# RasPi-BplusHAT.net
KiCad netlist of a schematic drawn in EAGLE
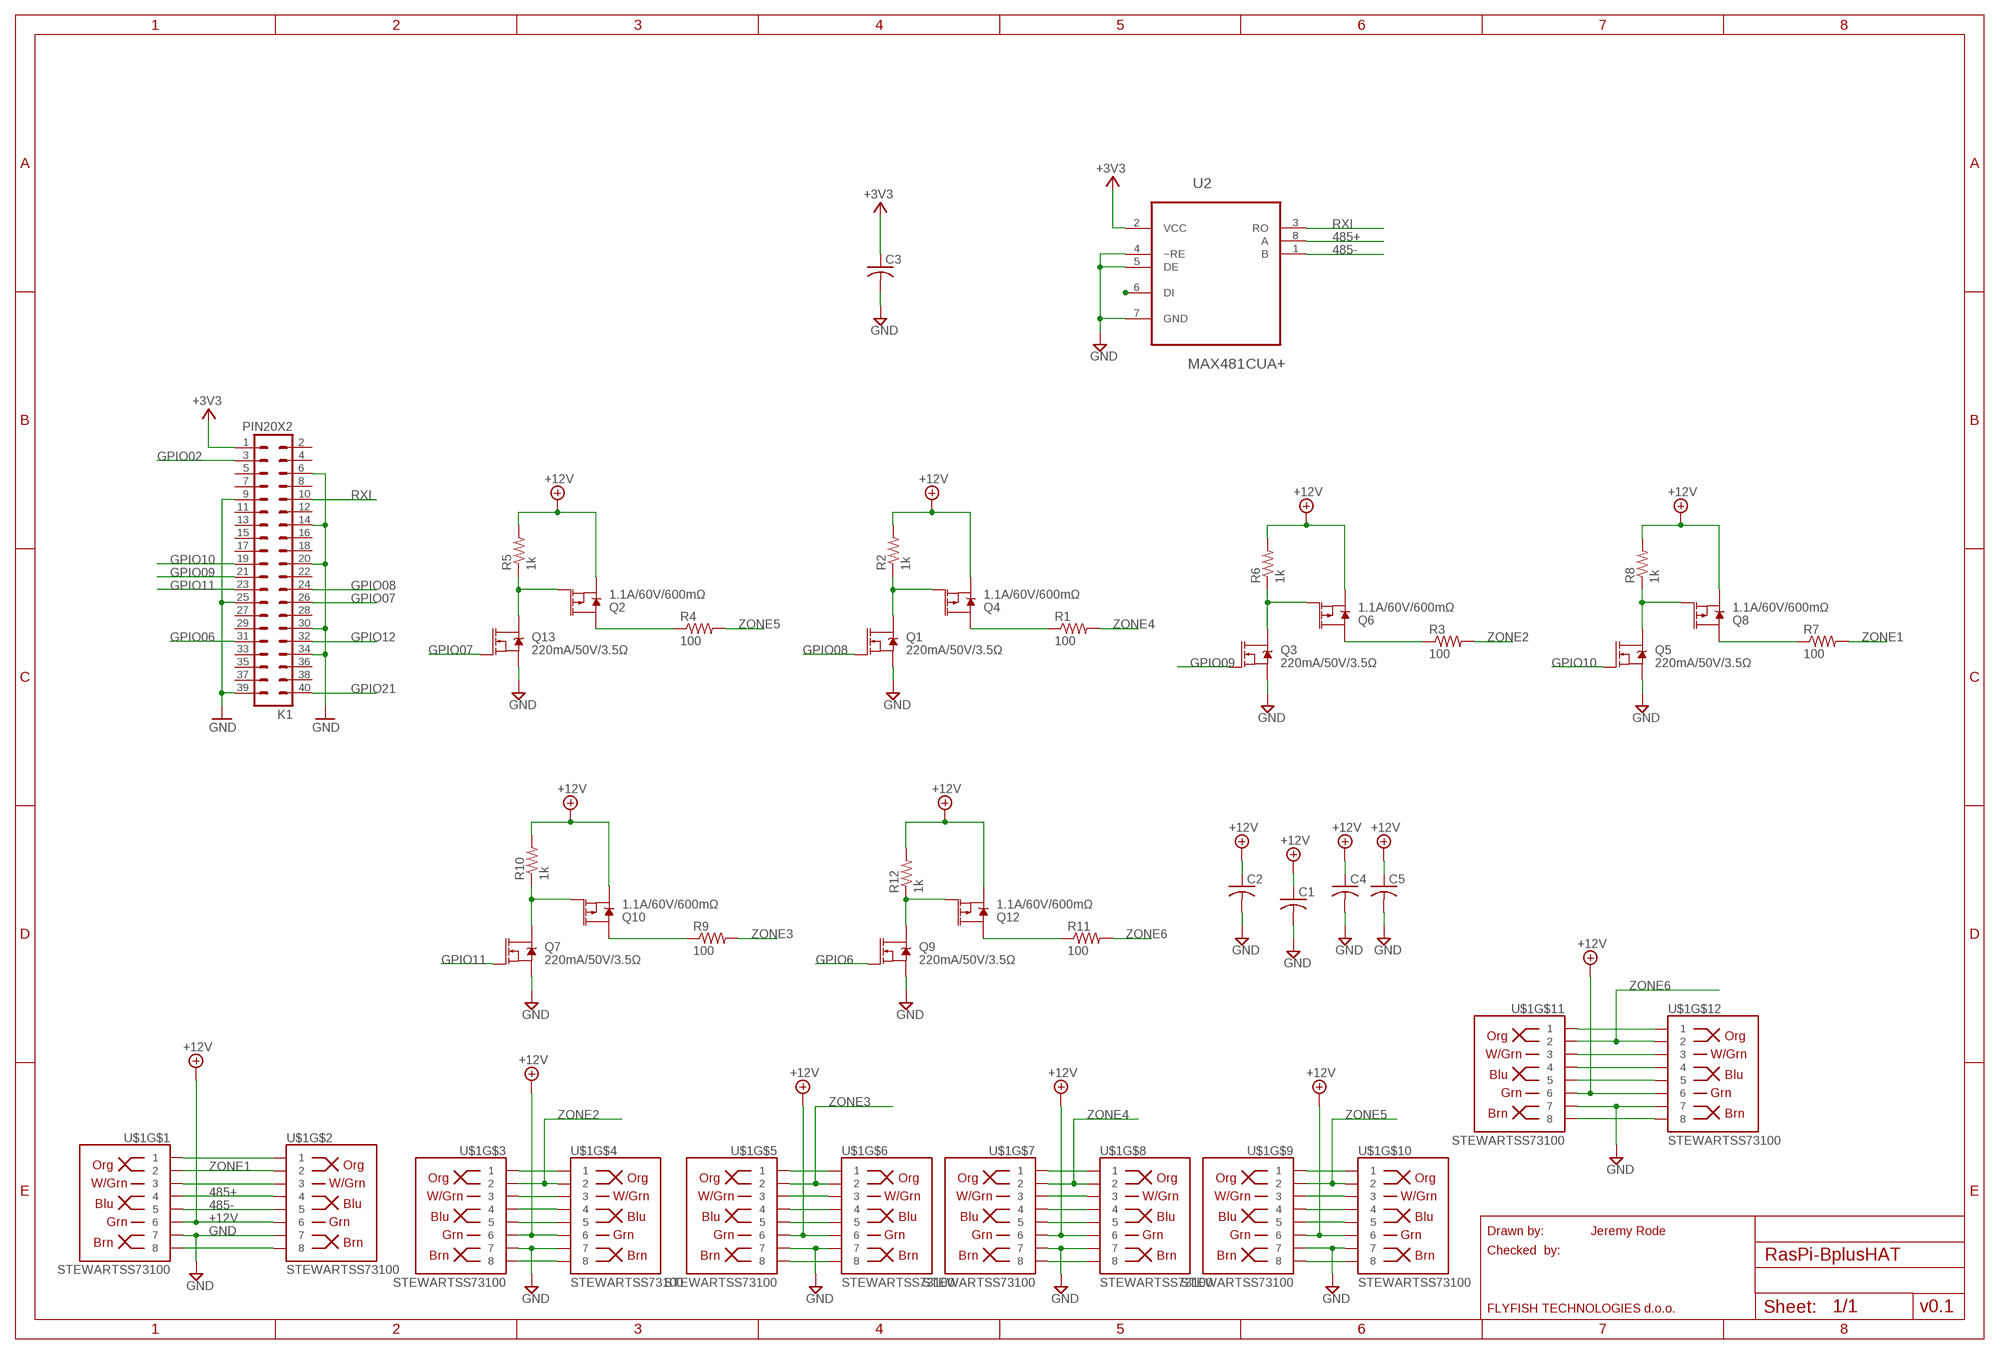
[diagram p0: schematic, sheet 1]

(export (version "E")
  (design (tool "Eeschema 10.0.6"))
  (components
    (comp (ref "C1")
      (value "C-USC0805")
      (footprint "eagle-import:C0805")
      (libsource (lib "eagle-import") (part "C-USC0805"))
    )
    (comp (ref "C2")
      (value "C-USC0805")
      (footprint "eagle-import:C0805")
      (libsource (lib "eagle-import") (part "C-USC0805"))
    )
    (comp (ref "C3")
      (value "C-USC0805")
      (footprint "eagle-import:C0805")
      (libsource (lib "eagle-import") (part "C-USC0805"))
    )
    (comp (ref "C4")
      (value "C-USC0805")
      (footprint "eagle-import:C0805")
      (libsource (lib "eagle-import") (part "C-USC0805"))
    )
    (comp (ref "C5")
      (value "C-USC0805")
      (footprint "eagle-import:C0805")
      (libsource (lib "eagle-import") (part "C-USC0805"))
    )
    (comp (ref "K1")
      (value "PIN20X2")
      (footprint "eagle-import:PIN_20X2")
      (libsource (lib "eagle-import") (part "PIN20X2"))
    )
    (comp (ref "Q1")
      (value "220mA/50V/3.5Ω")
      (footprint "eagle-import:SOT23-3")
      (libsource (lib "eagle-import") (part "MOSFET-NCH-BSS138"))
    )
    (comp (ref "Q2")
      (value "1.1A/60V/600mΩ")
      (footprint "eagle-import:SOT23-3")
      (libsource (lib "eagle-import") (part "MOSFET_PCH-SI2309DS"))
    )
    (comp (ref "Q3")
      (value "220mA/50V/3.5Ω")
      (footprint "eagle-import:SOT23-3")
      (libsource (lib "eagle-import") (part "MOSFET-NCH-BSS138"))
    )
    (comp (ref "Q4")
      (value "1.1A/60V/600mΩ")
      (footprint "eagle-import:SOT23-3")
      (libsource (lib "eagle-import") (part "MOSFET_PCH-SI2309DS"))
    )
    (comp (ref "Q5")
      (value "220mA/50V/3.5Ω")
      (footprint "eagle-import:SOT23-3")
      (libsource (lib "eagle-import") (part "MOSFET-NCH-BSS138"))
    )
    (comp (ref "Q6")
      (value "1.1A/60V/600mΩ")
      (footprint "eagle-import:SOT23-3")
      (libsource (lib "eagle-import") (part "MOSFET_PCH-SI2309DS"))
    )
    (comp (ref "Q7")
      (value "220mA/50V/3.5Ω")
      (footprint "eagle-import:SOT23-3")
      (libsource (lib "eagle-import") (part "MOSFET-NCH-BSS138"))
    )
    (comp (ref "Q8")
      (value "1.1A/60V/600mΩ")
      (footprint "eagle-import:SOT23-3")
      (libsource (lib "eagle-import") (part "MOSFET_PCH-SI2309DS"))
    )
    (comp (ref "Q9")
      (value "220mA/50V/3.5Ω")
      (footprint "eagle-import:SOT23-3")
      (libsource (lib "eagle-import") (part "MOSFET-NCH-BSS138"))
    )
    (comp (ref "Q10")
      (value "1.1A/60V/600mΩ")
      (footprint "eagle-import:SOT23-3")
      (libsource (lib "eagle-import") (part "MOSFET_PCH-SI2309DS"))
    )
    (comp (ref "Q12")
      (value "1.1A/60V/600mΩ")
      (footprint "eagle-import:SOT23-3")
      (libsource (lib "eagle-import") (part "MOSFET_PCH-SI2309DS"))
    )
    (comp (ref "Q13")
      (value "220mA/50V/3.5Ω")
      (footprint "eagle-import:SOT23-3")
      (libsource (lib "eagle-import") (part "MOSFET-NCH-BSS138"))
    )
    (comp (ref "R1")
      (value "100")
      (footprint "eagle-import:R0805")
      (libsource (lib "eagle-import") (part "R-US_R0805"))
    )
    (comp (ref "R2")
      (value "1k")
      (footprint "eagle-import:R0805")
      (libsource (lib "eagle-import") (part "R-US_R0805"))
    )
    (comp (ref "R3")
      (value "100")
      (footprint "eagle-import:R0805")
      (libsource (lib "eagle-import") (part "R-US_R0805"))
    )
    (comp (ref "R4")
      (value "100")
      (footprint "eagle-import:R0805")
      (libsource (lib "eagle-import") (part "R-US_R0805"))
    )
    (comp (ref "R5")
      (value "1k")
      (footprint "eagle-import:R0805")
      (libsource (lib "eagle-import") (part "R-US_R0805"))
    )
    (comp (ref "R6")
      (value "1k")
      (footprint "eagle-import:R0805")
      (libsource (lib "eagle-import") (part "R-US_R0805"))
    )
    (comp (ref "R7")
      (value "100")
      (footprint "eagle-import:R0805")
      (libsource (lib "eagle-import") (part "R-US_R0805"))
    )
    (comp (ref "R8")
      (value "1k")
      (footprint "eagle-import:R0805")
      (libsource (lib "eagle-import") (part "R-US_R0805"))
    )
    (comp (ref "R9")
      (value "100")
      (footprint "eagle-import:R0805")
      (libsource (lib "eagle-import") (part "R-US_R0805"))
    )
    (comp (ref "R10")
      (value "1k")
      (footprint "eagle-import:R0805")
      (libsource (lib "eagle-import") (part "R-US_R0805"))
    )
    (comp (ref "R11")
      (value "100")
      (footprint "eagle-import:R0805")
      (libsource (lib "eagle-import") (part "R-US_R0805"))
    )
    (comp (ref "R12")
      (value "1k")
      (footprint "eagle-import:R0805")
      (libsource (lib "eagle-import") (part "R-US_R0805"))
    )
    (comp (ref "U$1")
      (value "STEWARTSS73100")
      (footprint "eagle-import:STEWARTSS73100")
      (libsource (lib "eagle-import") (part "STEWARTSS73100"))
    )
    (comp (ref "U2")
      (value "MAX481CUA+")
      (footprint "eagle-import:SOP65P490X110-8N")
      (fields (field (name "MF") "Maxim Integrated"))
      (libsource (lib "eagle-import") (part "MAX481CUA+"))
    )
  )
  (nets
    (net (code "1") (name "+3V3") (class "Default")
      (node (ref "C3") (pin "1") (pinfunction "1_1") (pintype "passive"))
      (node (ref "K1") (pin "1") (pinfunction "1_1") (pintype "passive"))
      (node (ref "U2") (pin "2") (pinfunction "VCC_2") (pintype "power_in"))
    )
    (net (code "2") (name "+12V") (class "Default")
      (node (ref "C1") (pin "1") (pinfunction "1_1") (pintype "passive"))
      (node (ref "C2") (pin "1") (pinfunction "1_1") (pintype "passive"))
      (node (ref "C4") (pin "1") (pinfunction "1_1") (pintype "passive"))
      (node (ref "C5") (pin "1") (pinfunction "1_1") (pintype "passive"))
      (node (ref "Q10") (pin "2") (pinfunction "S_2") (pintype "bidirectional"))
      (node (ref "Q12") (pin "2") (pinfunction "S_2") (pintype "bidirectional"))
      (node (ref "Q2") (pin "2") (pinfunction "S_2") (pintype "bidirectional"))
      (node (ref "Q4") (pin "2") (pinfunction "S_2") (pintype "bidirectional"))
      (node (ref "Q6") (pin "2") (pinfunction "S_2") (pintype "bidirectional"))
      (node (ref "Q8") (pin "2") (pinfunction "S_2") (pintype "bidirectional"))
      (node (ref "R10") (pin "2") (pinfunction "2_2") (pintype "passive"))
      (node (ref "R12") (pin "2") (pinfunction "2_2") (pintype "passive"))
      (node (ref "R2") (pin "2") (pinfunction "2_2") (pintype "passive"))
      (node (ref "R5") (pin "2") (pinfunction "2_2") (pintype "passive"))
      (node (ref "R6") (pin "2") (pinfunction "2_2") (pintype "passive"))
      (node (ref "R8") (pin "2") (pinfunction "2_2") (pintype "passive"))
      (node (ref "U$1") (pin "P$14") (pinfunction "6_P$14") (pintype "bidirectional"))
      (node (ref "U$1") (pin "P$22") (pinfunction "6_P$22") (pintype "bidirectional"))
      (node (ref "U$1") (pin "P$30") (pinfunction "6_P$30") (pintype "bidirectional"))
      (node (ref "U$1") (pin "P$38") (pinfunction "6_P$38") (pintype "bidirectional"))
      (node (ref "U$1") (pin "P$46") (pinfunction "6_P$46") (pintype "bidirectional"))
      (node (ref "U$1") (pin "P$54") (pinfunction "6_P$54") (pintype "bidirectional"))
      (node (ref "U$1") (pin "P$6") (pinfunction "6_P$6") (pintype "bidirectional"))
      (node (ref "U$1") (pin "P$62") (pinfunction "6_P$62") (pintype "bidirectional"))
      (node (ref "U$1") (pin "P$70") (pinfunction "6_P$70") (pintype "bidirectional"))
      (node (ref "U$1") (pin "P$78") (pinfunction "6_P$78") (pintype "bidirectional"))
      (node (ref "U$1") (pin "P$86") (pinfunction "6_P$86") (pintype "bidirectional"))
      (node (ref "U$1") (pin "P$94") (pinfunction "6_P$94") (pintype "bidirectional"))
    )
    (net (code "3") (name "/485+") (class "Default")
      (node (ref "U$1") (pin "P$12") (pinfunction "4_P$12") (pintype "bidirectional"))
      (node (ref "U$1") (pin "P$4") (pinfunction "4_P$4") (pintype "bidirectional"))
      (node (ref "U2") (pin "8") (pinfunction "A_8") (pintype "bidirectional"))
    )
    (net (code "4") (name "/485-") (class "Default")
      (node (ref "U$1") (pin "P$13") (pinfunction "5_P$13") (pintype "bidirectional"))
      (node (ref "U$1") (pin "P$5") (pinfunction "5_P$5") (pintype "bidirectional"))
      (node (ref "U2") (pin "1") (pinfunction "B_1") (pintype "bidirectional"))
    )
    (net (code "5") (name "/GPIO02") (class "Default")
      (node (ref "K1") (pin "3") (pinfunction "3_3") (pintype "passive"))
    )
    (net (code "6") (name "/GPIO06") (class "Default")
      (node (ref "K1") (pin "31") (pinfunction "31_31") (pintype "passive"))
    )
    (net (code "7") (name "/GPIO6") (class "Default")
      (node (ref "Q9") (pin "1") (pinfunction "G_1") (pintype "bidirectional"))
    )
    (net (code "8") (name "/GPIO07") (class "Default")
      (node (ref "K1") (pin "26") (pinfunction "26_26") (pintype "passive"))
      (node (ref "Q13") (pin "1") (pinfunction "G_1") (pintype "bidirectional"))
    )
    (net (code "9") (name "/GPIO08") (class "Default")
      (node (ref "K1") (pin "24") (pinfunction "24_24") (pintype "passive"))
      (node (ref "Q1") (pin "1") (pinfunction "G_1") (pintype "bidirectional"))
    )
    (net (code "10") (name "/GPIO09") (class "Default")
      (node (ref "K1") (pin "21") (pinfunction "21_21") (pintype "passive"))
      (node (ref "Q3") (pin "1") (pinfunction "G_1") (pintype "bidirectional"))
    )
    (net (code "11") (name "/GPIO10") (class "Default")
      (node (ref "K1") (pin "19") (pinfunction "19_19") (pintype "passive"))
      (node (ref "Q5") (pin "1") (pinfunction "G_1") (pintype "bidirectional"))
    )
    (net (code "12") (name "/GPIO11") (class "Default")
      (node (ref "K1") (pin "23") (pinfunction "23_23") (pintype "passive"))
      (node (ref "Q7") (pin "1") (pinfunction "G_1") (pintype "bidirectional"))
    )
    (net (code "13") (name "/GPIO12") (class "Default")
      (node (ref "K1") (pin "32") (pinfunction "32_32") (pintype "passive"))
    )
    (net (code "14") (name "/GPIO21") (class "Default")
      (node (ref "K1") (pin "40") (pinfunction "40_40") (pintype "passive"))
    )
    (net (code "15") (name "/RXI") (class "Default")
      (node (ref "K1") (pin "10") (pinfunction "10_10") (pintype "passive"))
      (node (ref "U2") (pin "3") (pinfunction "RO_3") (pintype "output"))
    )
    (net (code "16") (name "/ZONE1") (class "Default")
      (node (ref "R7") (pin "2") (pinfunction "2_2") (pintype "passive"))
      (node (ref "U$1") (pin "P$10") (pinfunction "2_P$10") (pintype "bidirectional"))
      (node (ref "U$1") (pin "P$2") (pinfunction "2_P$2") (pintype "bidirectional"))
    )
    (net (code "17") (name "/ZONE2") (class "Default")
      (node (ref "R3") (pin "2") (pinfunction "2_2") (pintype "passive"))
      (node (ref "U$1") (pin "P$18") (pinfunction "2_P$18") (pintype "bidirectional"))
      (node (ref "U$1") (pin "P$26") (pinfunction "2_P$26") (pintype "bidirectional"))
    )
    (net (code "18") (name "/ZONE3") (class "Default")
      (node (ref "R9") (pin "2") (pinfunction "2_2") (pintype "passive"))
      (node (ref "U$1") (pin "P$34") (pinfunction "2_P$34") (pintype "bidirectional"))
      (node (ref "U$1") (pin "P$42") (pinfunction "2_P$42") (pintype "bidirectional"))
    )
    (net (code "19") (name "/ZONE4") (class "Default")
      (node (ref "R1") (pin "2") (pinfunction "2_2") (pintype "passive"))
      (node (ref "U$1") (pin "P$50") (pinfunction "2_P$50") (pintype "bidirectional"))
      (node (ref "U$1") (pin "P$58") (pinfunction "2_P$58") (pintype "bidirectional"))
    )
    (net (code "20") (name "/ZONE5") (class "Default")
      (node (ref "R4") (pin "2") (pinfunction "2_2") (pintype "passive"))
      (node (ref "U$1") (pin "P$66") (pinfunction "2_P$66") (pintype "bidirectional"))
      (node (ref "U$1") (pin "P$74") (pinfunction "2_P$74") (pintype "bidirectional"))
    )
    (net (code "21") (name "/ZONE6") (class "Default")
      (node (ref "R11") (pin "2") (pinfunction "2_2") (pintype "passive"))
      (node (ref "U$1") (pin "P$82") (pinfunction "2_P$82") (pintype "bidirectional"))
      (node (ref "U$1") (pin "P$90") (pinfunction "2_P$90") (pintype "bidirectional"))
    )
    (net (code "22") (name "GND") (class "Default")
      (node (ref "C1") (pin "2") (pinfunction "2_2") (pintype "passive"))
      (node (ref "C2") (pin "2") (pinfunction "2_2") (pintype "passive"))
      (node (ref "C3") (pin "2") (pinfunction "2_2") (pintype "passive"))
      (node (ref "C4") (pin "2") (pinfunction "2_2") (pintype "passive"))
      (node (ref "C5") (pin "2") (pinfunction "2_2") (pintype "passive"))
      (node (ref "K1") (pin "14") (pinfunction "14_14") (pintype "passive"))
      (node (ref "K1") (pin "20") (pinfunction "20_20") (pintype "passive"))
      (node (ref "K1") (pin "25") (pinfunction "25_25") (pintype "passive"))
      (node (ref "K1") (pin "30") (pinfunction "30_30") (pintype "passive"))
      (node (ref "K1") (pin "34") (pinfunction "34_34") (pintype "passive"))
      (node (ref "K1") (pin "39") (pinfunction "39_39") (pintype "passive"))
      (node (ref "K1") (pin "6") (pinfunction "6_6") (pintype "passive"))
      (node (ref "K1") (pin "9") (pinfunction "9_9") (pintype "passive"))
      (node (ref "Q1") (pin "2") (pinfunction "S_2") (pintype "bidirectional"))
      (node (ref "Q13") (pin "2") (pinfunction "S_2") (pintype "bidirectional"))
      (node (ref "Q3") (pin "2") (pinfunction "S_2") (pintype "bidirectional"))
      (node (ref "Q5") (pin "2") (pinfunction "S_2") (pintype "bidirectional"))
      (node (ref "Q7") (pin "2") (pinfunction "S_2") (pintype "bidirectional"))
      (node (ref "Q9") (pin "2") (pinfunction "S_2") (pintype "bidirectional"))
      (node (ref "U$1") (pin "P$15") (pinfunction "7_P$15") (pintype "bidirectional"))
      (node (ref "U$1") (pin "P$23") (pinfunction "7_P$23") (pintype "bidirectional"))
      (node (ref "U$1") (pin "P$31") (pinfunction "7_P$31") (pintype "bidirectional"))
      (node (ref "U$1") (pin "P$39") (pinfunction "7_P$39") (pintype "bidirectional"))
      (node (ref "U$1") (pin "P$47") (pinfunction "7_P$47") (pintype "bidirectional"))
      (node (ref "U$1") (pin "P$55") (pinfunction "7_P$55") (pintype "bidirectional"))
      (node (ref "U$1") (pin "P$63") (pinfunction "7_P$63") (pintype "bidirectional"))
      (node (ref "U$1") (pin "P$7") (pinfunction "7_P$7") (pintype "bidirectional"))
      (node (ref "U$1") (pin "P$71") (pinfunction "7_P$71") (pintype "bidirectional"))
      (node (ref "U$1") (pin "P$79") (pinfunction "7_P$79") (pintype "bidirectional"))
      (node (ref "U$1") (pin "P$87") (pinfunction "7_P$87") (pintype "bidirectional"))
      (node (ref "U$1") (pin "P$95") (pinfunction "7_P$95") (pintype "bidirectional"))
      (node (ref "U2") (pin "4") (pinfunction "~{RE}_4") (pintype "input"))
      (node (ref "U2") (pin "5") (pinfunction "DE_5") (pintype "input"))
      (node (ref "U2") (pin "7") (pinfunction "GND_7") (pintype "passive"))
    )
    (net (code "23") (name "Net-(Q1-D)") (class "Default")
      (node (ref "Q1") (pin "3") (pinfunction "D_3") (pintype "bidirectional"))
      (node (ref "Q4") (pin "1") (pinfunction "G_1") (pintype "bidirectional"))
      (node (ref "R2") (pin "1") (pinfunction "1_1") (pintype "passive"))
    )
    (net (code "24") (name "Net-(Q2-D)") (class "Default")
      (node (ref "Q2") (pin "3") (pinfunction "D_3") (pintype "bidirectional"))
      (node (ref "R4") (pin "1") (pinfunction "1_1") (pintype "passive"))
    )
    (net (code "25") (name "Net-(Q3-D)") (class "Default")
      (node (ref "Q3") (pin "3") (pinfunction "D_3") (pintype "bidirectional"))
      (node (ref "Q6") (pin "1") (pinfunction "G_1") (pintype "bidirectional"))
      (node (ref "R6") (pin "1") (pinfunction "1_1") (pintype "passive"))
    )
    (net (code "26") (name "Net-(Q4-D)") (class "Default")
      (node (ref "Q4") (pin "3") (pinfunction "D_3") (pintype "bidirectional"))
      (node (ref "R1") (pin "1") (pinfunction "1_1") (pintype "passive"))
    )
    (net (code "27") (name "Net-(Q5-D)") (class "Default")
      (node (ref "Q5") (pin "3") (pinfunction "D_3") (pintype "bidirectional"))
      (node (ref "Q8") (pin "1") (pinfunction "G_1") (pintype "bidirectional"))
      (node (ref "R8") (pin "1") (pinfunction "1_1") (pintype "passive"))
    )
    (net (code "28") (name "Net-(Q6-D)") (class "Default")
      (node (ref "Q6") (pin "3") (pinfunction "D_3") (pintype "bidirectional"))
      (node (ref "R3") (pin "1") (pinfunction "1_1") (pintype "passive"))
    )
    (net (code "29") (name "Net-(Q8-D)") (class "Default")
      (node (ref "Q8") (pin "3") (pinfunction "D_3") (pintype "bidirectional"))
      (node (ref "R7") (pin "1") (pinfunction "1_1") (pintype "passive"))
    )
    (net (code "30") (name "Net-(Q10-D)") (class "Default")
      (node (ref "Q10") (pin "3") (pinfunction "D_3") (pintype "bidirectional"))
      (node (ref "R9") (pin "1") (pinfunction "1_1") (pintype "passive"))
    )
    (net (code "31") (name "Net-(Q10-G)") (class "Default")
      (node (ref "Q10") (pin "1") (pinfunction "G_1") (pintype "bidirectional"))
      (node (ref "Q7") (pin "3") (pinfunction "D_3") (pintype "bidirectional"))
      (node (ref "R10") (pin "1") (pinfunction "1_1") (pintype "passive"))
    )
    (net (code "32") (name "Net-(Q12-D)") (class "Default")
      (node (ref "Q12") (pin "3") (pinfunction "D_3") (pintype "bidirectional"))
      (node (ref "R11") (pin "1") (pinfunction "1_1") (pintype "passive"))
    )
    (net (code "33") (name "Net-(Q12-G)") (class "Default")
      (node (ref "Q12") (pin "1") (pinfunction "G_1") (pintype "bidirectional"))
      (node (ref "Q9") (pin "3") (pinfunction "D_3") (pintype "bidirectional"))
      (node (ref "R12") (pin "1") (pinfunction "1_1") (pintype "passive"))
    )
    (net (code "34") (name "Net-(Q13-D)") (class "Default")
      (node (ref "Q13") (pin "3") (pinfunction "D_3") (pintype "bidirectional"))
      (node (ref "Q2") (pin "1") (pinfunction "G_1") (pintype "bidirectional"))
      (node (ref "R5") (pin "1") (pinfunction "1_1") (pintype "passive"))
    )
    (net (code "35") (name "Net-(U$1A-1)") (class "Default")
      (node (ref "U$1") (pin "P$1") (pinfunction "1_P$1") (pintype "bidirectional"))
      (node (ref "U$1") (pin "P$9") (pinfunction "1_P$9") (pintype "bidirectional"))
    )
    (net (code "36") (name "Net-(U$1A-3)") (class "Default")
      (node (ref "U$1") (pin "P$11") (pinfunction "3_P$11") (pintype "bidirectional"))
      (node (ref "U$1") (pin "P$3") (pinfunction "3_P$3") (pintype "bidirectional"))
    )
    (net (code "37") (name "Net-(U$1A-8)") (class "Default")
      (node (ref "U$1") (pin "P$16") (pinfunction "8_P$16") (pintype "bidirectional"))
      (node (ref "U$1") (pin "P$8") (pinfunction "8_P$8") (pintype "bidirectional"))
    )
    (net (code "38") (name "Net-(U$1B-1)") (class "Default")
      (node (ref "U$1") (pin "P$65") (pinfunction "1_P$65") (pintype "bidirectional"))
      (node (ref "U$1") (pin "P$73") (pinfunction "1_P$73") (pintype "bidirectional"))
    )
    (net (code "39") (name "Net-(U$1B-3)") (class "Default")
      (node (ref "U$1") (pin "P$67") (pinfunction "3_P$67") (pintype "bidirectional"))
      (node (ref "U$1") (pin "P$75") (pinfunction "3_P$75") (pintype "bidirectional"))
    )
    (net (code "40") (name "Net-(U$1B-4)") (class "Default")
      (node (ref "U$1") (pin "P$68") (pinfunction "4_P$68") (pintype "bidirectional"))
      (node (ref "U$1") (pin "P$76") (pinfunction "4_P$76") (pintype "bidirectional"))
    )
    (net (code "41") (name "Net-(U$1B-5)") (class "Default")
      (node (ref "U$1") (pin "P$69") (pinfunction "5_P$69") (pintype "bidirectional"))
      (node (ref "U$1") (pin "P$77") (pinfunction "5_P$77") (pintype "bidirectional"))
    )
    (net (code "42") (name "Net-(U$1B-8)") (class "Default")
      (node (ref "U$1") (pin "P$72") (pinfunction "8_P$72") (pintype "bidirectional"))
      (node (ref "U$1") (pin "P$80") (pinfunction "8_P$80") (pintype "bidirectional"))
    )
    (net (code "43") (name "Net-(U$1C-1)") (class "Default")
      (node (ref "U$1") (pin "P$81") (pinfunction "1_P$81") (pintype "bidirectional"))
      (node (ref "U$1") (pin "P$89") (pinfunction "1_P$89") (pintype "bidirectional"))
    )
    (net (code "44") (name "Net-(U$1C-3)") (class "Default")
      (node (ref "U$1") (pin "P$83") (pinfunction "3_P$83") (pintype "bidirectional"))
      (node (ref "U$1") (pin "P$91") (pinfunction "3_P$91") (pintype "bidirectional"))
    )
    (net (code "45") (name "Net-(U$1C-4)") (class "Default")
      (node (ref "U$1") (pin "P$84") (pinfunction "4_P$84") (pintype "bidirectional"))
      (node (ref "U$1") (pin "P$92") (pinfunction "4_P$92") (pintype "bidirectional"))
    )
    (net (code "46") (name "Net-(U$1C-5)") (class "Default")
      (node (ref "U$1") (pin "P$85") (pinfunction "5_P$85") (pintype "bidirectional"))
      (node (ref "U$1") (pin "P$93") (pinfunction "5_P$93") (pintype "bidirectional"))
    )
    (net (code "47") (name "Net-(U$1C-8)") (class "Default")
      (node (ref "U$1") (pin "P$88") (pinfunction "8_P$88") (pintype "bidirectional"))
      (node (ref "U$1") (pin "P$96") (pinfunction "8_P$96") (pintype "bidirectional"))
    )
    (net (code "48") (name "Net-(U$1F-1)") (class "Default")
      (node (ref "U$1") (pin "P$17") (pinfunction "1_P$17") (pintype "bidirectional"))
      (node (ref "U$1") (pin "P$25") (pinfunction "1_P$25") (pintype "bidirectional"))
    )
    (net (code "49") (name "Net-(U$1F-3)") (class "Default")
      (node (ref "U$1") (pin "P$19") (pinfunction "3_P$19") (pintype "bidirectional"))
      (node (ref "U$1") (pin "P$27") (pinfunction "3_P$27") (pintype "bidirectional"))
    )
    (net (code "50") (name "Net-(U$1F-4)") (class "Default")
      (node (ref "U$1") (pin "P$20") (pinfunction "4_P$20") (pintype "bidirectional"))
      (node (ref "U$1") (pin "P$28") (pinfunction "4_P$28") (pintype "bidirectional"))
    )
    (net (code "51") (name "Net-(U$1F-5)") (class "Default")
      (node (ref "U$1") (pin "P$21") (pinfunction "5_P$21") (pintype "bidirectional"))
      (node (ref "U$1") (pin "P$29") (pinfunction "5_P$29") (pintype "bidirectional"))
    )
    (net (code "52") (name "Net-(U$1F-8)") (class "Default")
      (node (ref "U$1") (pin "P$24") (pinfunction "8_P$24") (pintype "bidirectional"))
      (node (ref "U$1") (pin "P$32") (pinfunction "8_P$32") (pintype "bidirectional"))
    )
    (net (code "53") (name "Net-(U$1H-1)") (class "Default")
      (node (ref "U$1") (pin "P$33") (pinfunction "1_P$33") (pintype "bidirectional"))
      (node (ref "U$1") (pin "P$41") (pinfunction "1_P$41") (pintype "bidirectional"))
    )
    (net (code "54") (name "Net-(U$1H-3)") (class "Default")
      (node (ref "U$1") (pin "P$35") (pinfunction "3_P$35") (pintype "bidirectional"))
      (node (ref "U$1") (pin "P$43") (pinfunction "3_P$43") (pintype "bidirectional"))
    )
    (net (code "55") (name "Net-(U$1H-4)") (class "Default")
      (node (ref "U$1") (pin "P$36") (pinfunction "4_P$36") (pintype "bidirectional"))
      (node (ref "U$1") (pin "P$44") (pinfunction "4_P$44") (pintype "bidirectional"))
    )
    (net (code "56") (name "Net-(U$1H-5)") (class "Default")
      (node (ref "U$1") (pin "P$37") (pinfunction "5_P$37") (pintype "bidirectional"))
      (node (ref "U$1") (pin "P$45") (pinfunction "5_P$45") (pintype "bidirectional"))
    )
    (net (code "57") (name "Net-(U$1H-8)") (class "Default")
      (node (ref "U$1") (pin "P$40") (pinfunction "8_P$40") (pintype "bidirectional"))
      (node (ref "U$1") (pin "P$48") (pinfunction "8_P$48") (pintype "bidirectional"))
    )
    (net (code "58") (name "Net-(U$1J-1)") (class "Default")
      (node (ref "U$1") (pin "P$49") (pinfunction "1_P$49") (pintype "bidirectional"))
      (node (ref "U$1") (pin "P$57") (pinfunction "1_P$57") (pintype "bidirectional"))
    )
    (net (code "59") (name "Net-(U$1J-3)") (class "Default")
      (node (ref "U$1") (pin "P$51") (pinfunction "3_P$51") (pintype "bidirectional"))
      (node (ref "U$1") (pin "P$59") (pinfunction "3_P$59") (pintype "bidirectional"))
    )
    (net (code "60") (name "Net-(U$1J-4)") (class "Default")
      (node (ref "U$1") (pin "P$52") (pinfunction "4_P$52") (pintype "bidirectional"))
      (node (ref "U$1") (pin "P$60") (pinfunction "4_P$60") (pintype "bidirectional"))
    )
    (net (code "61") (name "Net-(U$1J-5)") (class "Default")
      (node (ref "U$1") (pin "P$53") (pinfunction "5_P$53") (pintype "bidirectional"))
      (node (ref "U$1") (pin "P$61") (pinfunction "5_P$61") (pintype "bidirectional"))
    )
    (net (code "62") (name "Net-(U$1J-8)") (class "Default")
      (node (ref "U$1") (pin "P$56") (pinfunction "8_P$56") (pintype "bidirectional"))
      (node (ref "U$1") (pin "P$64") (pinfunction "8_P$64") (pintype "bidirectional"))
    )
    (net (code "63") (name "unconnected-(K1-Pad2)") (class "Default")
      (node (ref "K1") (pin "2") (pinfunction "2_2") (pintype "passive"))
    )
    (net (code "64") (name "unconnected-(K1-Pad4)") (class "Default")
      (node (ref "K1") (pin "4") (pinfunction "4_4") (pintype "passive"))
    )
    (net (code "65") (name "unconnected-(K1-Pad5)") (class "Default")
      (node (ref "K1") (pin "5") (pinfunction "5_5") (pintype "passive"))
    )
    (net (code "66") (name "unconnected-(K1-Pad7)") (class "Default")
      (node (ref "K1") (pin "7") (pinfunction "7_7") (pintype "passive"))
    )
    (net (code "67") (name "unconnected-(K1-Pad8)") (class "Default")
      (node (ref "K1") (pin "8") (pinfunction "8_8") (pintype "passive"))
    )
    (net (code "68") (name "unconnected-(K1-Pad11)") (class "Default")
      (node (ref "K1") (pin "11") (pinfunction "11_11") (pintype "passive"))
    )
    (net (code "69") (name "unconnected-(K1-Pad12)") (class "Default")
      (node (ref "K1") (pin "12") (pinfunction "12_12") (pintype "passive"))
    )
    (net (code "70") (name "unconnected-(K1-Pad13)") (class "Default")
      (node (ref "K1") (pin "13") (pinfunction "13_13") (pintype "passive"))
    )
    (net (code "71") (name "unconnected-(K1-Pad15)") (class "Default")
      (node (ref "K1") (pin "15") (pinfunction "15_15") (pintype "passive"))
    )
    (net (code "72") (name "unconnected-(K1-Pad16)") (class "Default")
      (node (ref "K1") (pin "16") (pinfunction "16_16") (pintype "passive"))
    )
    (net (code "73") (name "unconnected-(K1-Pad17)") (class "Default")
      (node (ref "K1") (pin "17") (pinfunction "17_17") (pintype "passive"))
    )
    (net (code "74") (name "unconnected-(K1-Pad18)") (class "Default")
      (node (ref "K1") (pin "18") (pinfunction "18_18") (pintype "passive"))
    )
    (net (code "75") (name "unconnected-(K1-Pad22)") (class "Default")
      (node (ref "K1") (pin "22") (pinfunction "22_22") (pintype "passive"))
    )
    (net (code "76") (name "unconnected-(K1-Pad27)") (class "Default")
      (node (ref "K1") (pin "27") (pinfunction "27_27") (pintype "passive"))
    )
    (net (code "77") (name "unconnected-(K1-Pad28)") (class "Default")
      (node (ref "K1") (pin "28") (pinfunction "28_28") (pintype "passive"))
    )
    (net (code "78") (name "unconnected-(K1-Pad29)") (class "Default")
      (node (ref "K1") (pin "29") (pinfunction "29_29") (pintype "passive"))
    )
    (net (code "79") (name "unconnected-(K1-Pad33)") (class "Default")
      (node (ref "K1") (pin "33") (pinfunction "33_33") (pintype "passive"))
    )
    (net (code "80") (name "unconnected-(K1-Pad35)") (class "Default")
      (node (ref "K1") (pin "35") (pinfunction "35_35") (pintype "passive"))
    )
    (net (code "81") (name "unconnected-(K1-Pad36)") (class "Default")
      (node (ref "K1") (pin "36") (pinfunction "36_36") (pintype "passive"))
    )
    (net (code "82") (name "unconnected-(K1-Pad37)") (class "Default")
      (node (ref "K1") (pin "37") (pinfunction "37_37") (pintype "passive"))
    )
    (net (code "83") (name "unconnected-(K1-Pad38)") (class "Default")
      (node (ref "K1") (pin "38") (pinfunction "38_38") (pintype "passive"))
    )
    (net (code "84") (name "unconnected-(U2-DI-Pad6)") (class "Default")
      (node (ref "U2") (pin "6") (pinfunction "DI_6") (pintype "input"))
    )
  )
)
